# Maqam_v3a.net
KiCad netlist of a schematic drawn in EAGLE
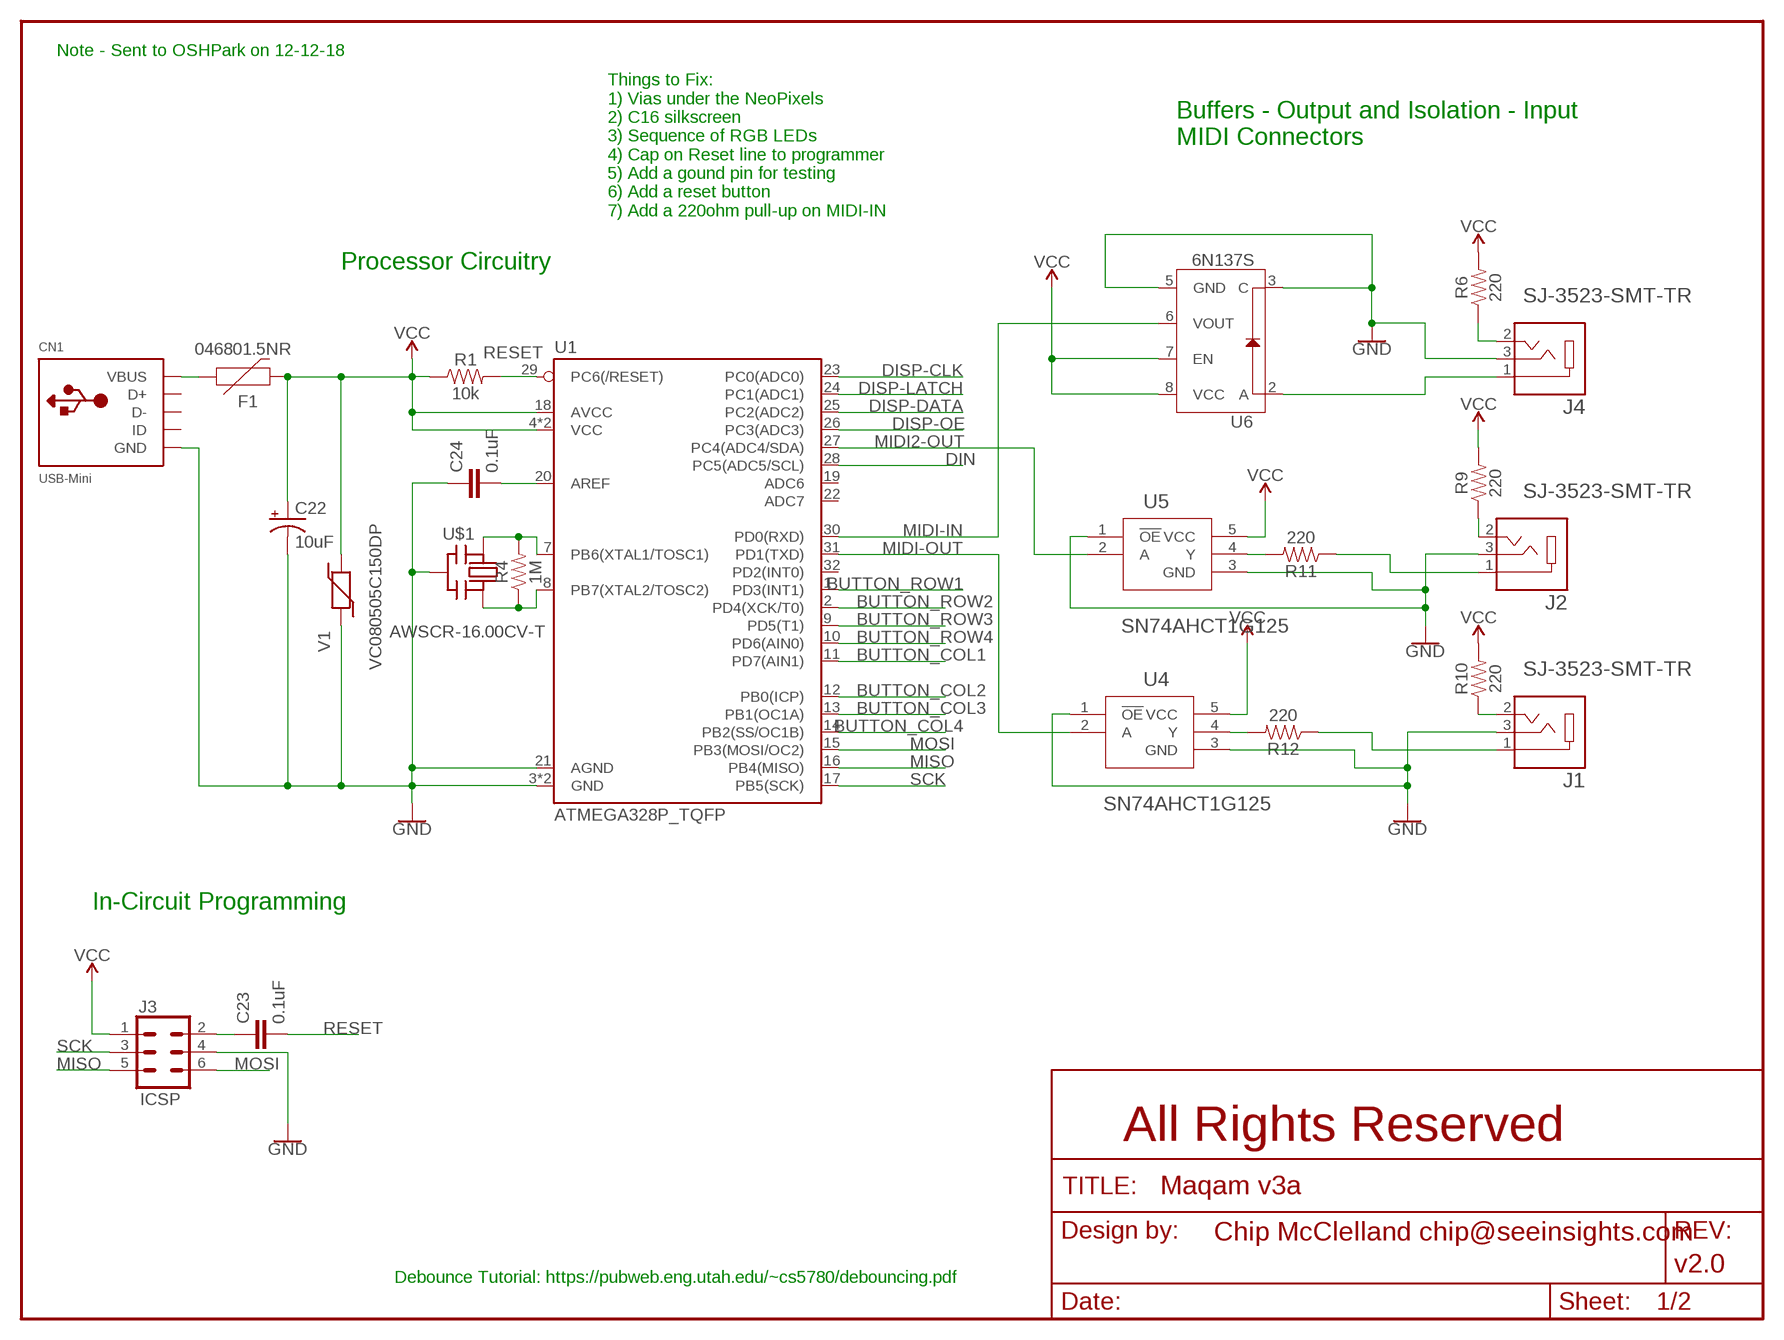
[diagram p0: schematic, sheet 1]
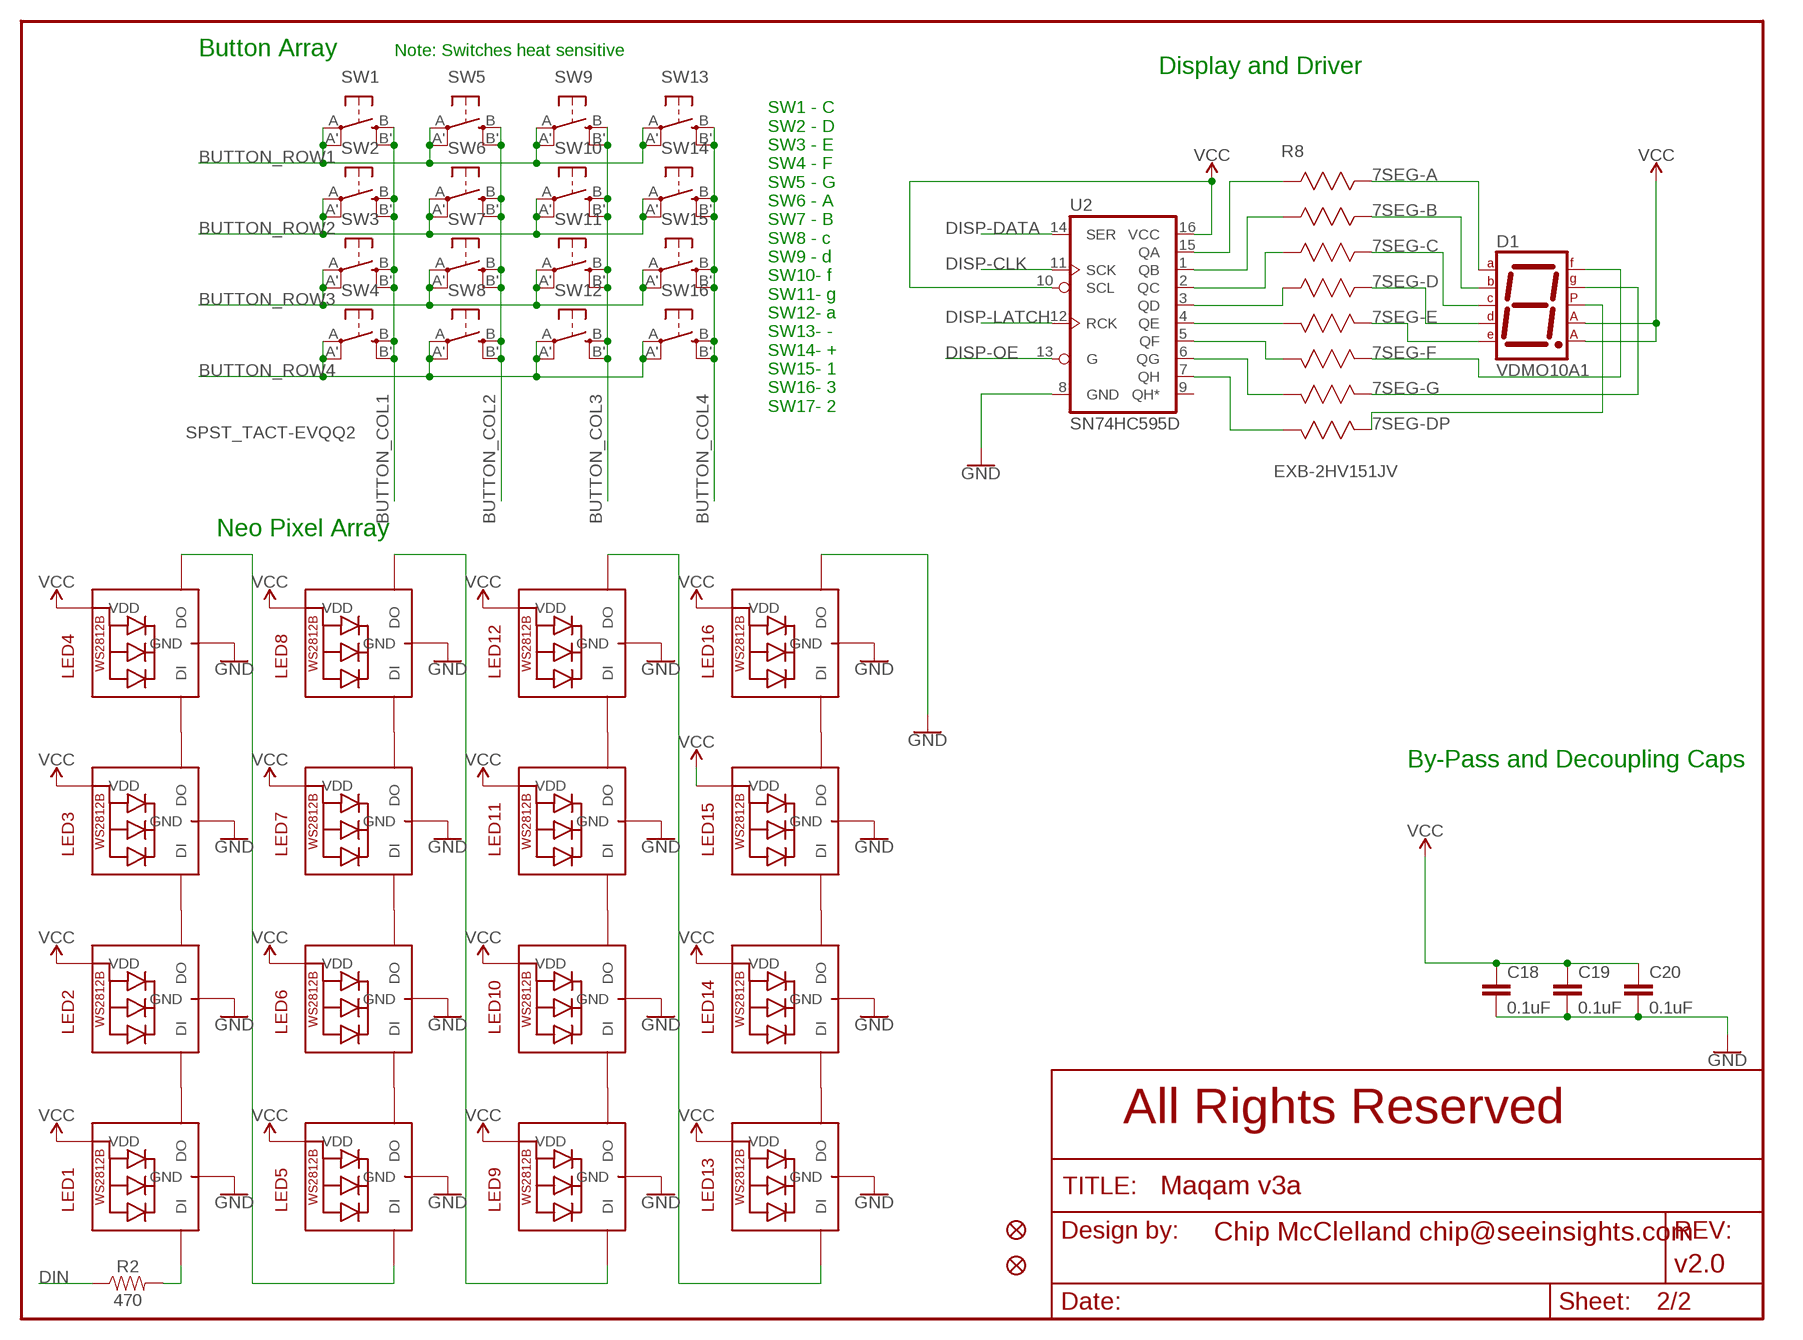
[diagram p1: schematic, sheet 2]

(export (version "E")
  (design (tool "Eeschema 10.0.6"))
  (components
    (comp (ref "C18")
      (value "0.1uF")
      (footprint "eagle-import:0805")
      (libsource (lib "eagle-import") (part "1.0UF-0805-25V-(+80/-20%)"))
    )
    (comp (ref "C19")
      (value "0.1uF")
      (footprint "eagle-import:0805")
      (libsource (lib "eagle-import") (part "1.0UF-0805-25V-(+80/-20%)"))
    )
    (comp (ref "C20")
      (value "0.1uF")
      (footprint "eagle-import:0805")
      (libsource (lib "eagle-import") (part "1.0UF-0805-25V-(+80/-20%)"))
    )
    (comp (ref "D1")
      (value "VDMO10A1")
      (footprint "eagle-import:7-SEG-SMD")
      (libsource (lib "eagle-import") (part "VDMO10A1"))
    )
    (comp (ref "FD1")
      (value "FIDUCIALUFIDUCIAL")
      (footprint "eagle-import:FIDUCIAL-MICRO")
      (libsource (lib "eagle-import") (part "FIDUCIALUFIDUCIAL"))
    )
    (comp (ref "FD2")
      (value "FIDUCIALUFIDUCIAL")
      (footprint "eagle-import:FIDUCIAL-MICRO")
      (libsource (lib "eagle-import") (part "FIDUCIALUFIDUCIAL"))
    )
    (comp (ref "FRAME1")
      (value "FRAME-LETTERNO_PACKAGE")
      (footprint "eagle-import:DUMMY")
      (fields
        (field (name "DESIGNER") "Chip McClelland chip@seeinsights.com")
        (field (name "REV") "v2.0")
        (field (name "VERSION") "v2.0")
        (field (name "DESIGNER_1") "Chip McClelland chip@seeinsights.com")
      )
      (libsource (lib "eagle-import") (part "FRAME-LETTERNO_PACKAGE"))
    )
    (comp (ref "LED1")
      (value "WS2812B3535")
      (footprint "eagle-import:LED3535")
      (libsource (lib "eagle-import") (part "WS2812B3535"))
    )
    (comp (ref "LED2")
      (value "WS2812B3535")
      (footprint "eagle-import:LED3535")
      (libsource (lib "eagle-import") (part "WS2812B3535"))
    )
    (comp (ref "LED3")
      (value "WS2812B3535")
      (footprint "eagle-import:LED3535")
      (libsource (lib "eagle-import") (part "WS2812B3535"))
    )
    (comp (ref "LED4")
      (value "WS2812B3535")
      (footprint "eagle-import:LED3535")
      (libsource (lib "eagle-import") (part "WS2812B3535"))
    )
    (comp (ref "LED5")
      (value "WS2812B3535")
      (footprint "eagle-import:LED3535")
      (libsource (lib "eagle-import") (part "WS2812B3535"))
    )
    (comp (ref "LED6")
      (value "WS2812B3535")
      (footprint "eagle-import:LED3535")
      (libsource (lib "eagle-import") (part "WS2812B3535"))
    )
    (comp (ref "LED7")
      (value "WS2812B3535")
      (footprint "eagle-import:LED3535")
      (libsource (lib "eagle-import") (part "WS2812B3535"))
    )
    (comp (ref "LED8")
      (value "WS2812B3535")
      (footprint "eagle-import:LED3535")
      (libsource (lib "eagle-import") (part "WS2812B3535"))
    )
    (comp (ref "LED9")
      (value "WS2812B3535")
      (footprint "eagle-import:LED3535")
      (libsource (lib "eagle-import") (part "WS2812B3535"))
    )
    (comp (ref "LED10")
      (value "WS2812B3535")
      (footprint "eagle-import:LED3535")
      (libsource (lib "eagle-import") (part "WS2812B3535"))
    )
    (comp (ref "LED11")
      (value "WS2812B3535")
      (footprint "eagle-import:LED3535")
      (libsource (lib "eagle-import") (part "WS2812B3535"))
    )
    (comp (ref "LED12")
      (value "WS2812B3535")
      (footprint "eagle-import:LED3535")
      (libsource (lib "eagle-import") (part "WS2812B3535"))
    )
    (comp (ref "LED13")
      (value "WS2812B3535")
      (footprint "eagle-import:LED3535")
      (libsource (lib "eagle-import") (part "WS2812B3535"))
    )
    (comp (ref "LED14")
      (value "WS2812B3535")
      (footprint "eagle-import:LED3535")
      (libsource (lib "eagle-import") (part "WS2812B3535"))
    )
    (comp (ref "LED15")
      (value "WS2812B3535")
      (footprint "eagle-import:LED3535")
      (libsource (lib "eagle-import") (part "WS2812B3535"))
    )
    (comp (ref "LED16")
      (value "WS2812B3535")
      (footprint "eagle-import:LED3535")
      (libsource (lib "eagle-import") (part "WS2812B3535"))
    )
    (comp (ref "R2")
      (value "470")
      (footprint "eagle-import:0805")
      (libsource (lib "eagle-import") (part "RESISTOR0805"))
    )
    (comp (ref "R8")
      (value "EXB-2HV151JV")
      (footprint "eagle-import:EXB2HV-L")
      (fields (field (name "MANUFACTURER_PART_NUMBER") "EXB2HV103JV"))
      (libsource (lib "eagle-import") (part "EXB-2HV103JVEXB2HV-L"))
    )
    (comp (ref "SW1")
      (value "SPST_TACT-EVQQ2")
      (footprint "eagle-import:EVQ-Q2")
      (libsource (lib "eagle-import") (part "SPST_TACT-EVQQ2"))
    )
    (comp (ref "SW2")
      (value "SPST_TACT-EVQQ2")
      (footprint "eagle-import:EVQ-Q2")
      (libsource (lib "eagle-import") (part "SPST_TACT-EVQQ2"))
    )
    (comp (ref "SW3")
      (value "SPST_TACT-EVQQ2")
      (footprint "eagle-import:EVQ-Q2")
      (libsource (lib "eagle-import") (part "SPST_TACT-EVQQ2"))
    )
    (comp (ref "SW4")
      (value "SPST_TACT-EVQQ2")
      (footprint "eagle-import:EVQ-Q2")
      (libsource (lib "eagle-import") (part "SPST_TACT-EVQQ2"))
    )
    (comp (ref "SW5")
      (value "SPST_TACT-EVQQ2")
      (footprint "eagle-import:EVQ-Q2")
      (libsource (lib "eagle-import") (part "SPST_TACT-EVQQ2"))
    )
    (comp (ref "SW6")
      (value "SPST_TACT-EVQQ2")
      (footprint "eagle-import:EVQ-Q2")
      (libsource (lib "eagle-import") (part "SPST_TACT-EVQQ2"))
    )
    (comp (ref "SW7")
      (value "SPST_TACT-EVQQ2")
      (footprint "eagle-import:EVQ-Q2")
      (libsource (lib "eagle-import") (part "SPST_TACT-EVQQ2"))
    )
    (comp (ref "SW8")
      (value "SPST_TACT-EVQQ2")
      (footprint "eagle-import:EVQ-Q2")
      (libsource (lib "eagle-import") (part "SPST_TACT-EVQQ2"))
    )
    (comp (ref "SW9")
      (value "SPST_TACT-EVQQ2")
      (footprint "eagle-import:EVQ-Q2")
      (libsource (lib "eagle-import") (part "SPST_TACT-EVQQ2"))
    )
    (comp (ref "SW10")
      (value "SPST_TACT-EVQQ2")
      (footprint "eagle-import:EVQ-Q2")
      (libsource (lib "eagle-import") (part "SPST_TACT-EVQQ2"))
    )
    (comp (ref "SW11")
      (value "SPST_TACT-EVQQ2")
      (footprint "eagle-import:EVQ-Q2")
      (libsource (lib "eagle-import") (part "SPST_TACT-EVQQ2"))
    )
    (comp (ref "SW12")
      (value "SPST_TACT-EVQQ2")
      (footprint "eagle-import:EVQ-Q2")
      (libsource (lib "eagle-import") (part "SPST_TACT-EVQQ2"))
    )
    (comp (ref "SW13")
      (value "SPST_TACT-EVQQ2")
      (footprint "eagle-import:EVQ-Q2")
      (libsource (lib "eagle-import") (part "SPST_TACT-EVQQ2"))
    )
    (comp (ref "SW14")
      (value "SPST_TACT-EVQQ2")
      (footprint "eagle-import:EVQ-Q2")
      (libsource (lib "eagle-import") (part "SPST_TACT-EVQQ2"))
    )
    (comp (ref "SW15")
      (value "SPST_TACT-EVQQ2")
      (footprint "eagle-import:EVQ-Q2")
      (libsource (lib "eagle-import") (part "SPST_TACT-EVQQ2"))
    )
    (comp (ref "SW16")
      (value "SPST_TACT-EVQQ2")
      (footprint "eagle-import:EVQ-Q2")
      (libsource (lib "eagle-import") (part "SPST_TACT-EVQQ2"))
    )
    (comp (ref "U2")
      (value "SN74HC595D")
      (footprint "eagle-import:SO16")
      (libsource (lib "eagle-import") (part "74595DHC"))
    )
    (comp (ref "C22")
      (value "10uF")
      (footprint "eagle-import:EIA3216")
      (libsource (lib "eagle-import") (part "10UF-POLAR-EIA3216-16V-10%(TANT)"))
    )
    (comp (ref "C23")
      (value "0.1uF")
      (footprint "eagle-import:0805")
      (libsource (lib "eagle-import") (part "1.0UF-0805-25V-(+80/-20%)"))
    )
    (comp (ref "C24")
      (value "0.1uF")
      (footprint "eagle-import:0805")
      (libsource (lib "eagle-import") (part "1.0UF-0805-25V-(+80/-20%)"))
    )
    (comp (ref "CN1")
      (value "USB-Mini")
      (footprint "eagle-import:USB-MINIB")
      (libsource (lib "eagle-import") (part "USBMINIB"))
    )
    (comp (ref "F1")
      (value "046801.5NR")
      (footprint "eagle-import:1206")
      (libsource (lib "eagle-import") (part "PPTC_HALF-AMP"))
    )
    (comp (ref "FRAME2")
      (value "FRAME-LETTERNO_PACKAGE")
      (footprint "eagle-import:DUMMY")
      (fields
        (field (name "DESIGNER") "Chip McClelland chip@seeinsights.com")
        (field (name "REV") "v2.0")
        (field (name "VERSION") "v2.0")
        (field (name "DESIGNER_1") "Chip McClelland chip@seeinsights.com")
      )
      (libsource (lib "eagle-import") (part "FRAME-LETTERNO_PACKAGE"))
    )
    (comp (ref "J1")
      (value "SJ-3523-SMT-TR")
      (footprint "eagle-import:CUI_SJ-3523-SMT-TR")
      (fields (field (name "DIGI-KEY_PART_NUMBER") "CP-3523SJCT-ND") (field (name "MF") "CUI Inc."))
      (libsource (lib "eagle-import") (part "SJ-3523-SMT-TR"))
    )
    (comp (ref "J2")
      (value "SJ-3523-SMT-TR")
      (footprint "eagle-import:CUI_SJ-3523-SMT-TR")
      (fields (field (name "DIGI-KEY_PART_NUMBER") "CP-3523SJCT-ND") (field (name "MF") "CUI Inc."))
      (libsource (lib "eagle-import") (part "SJ-3523-SMT-TR"))
    )
    (comp (ref "J3")
      (value "ICSP")
      (footprint "eagle-import:2X3-SHROUDED")
      (libsource (lib "eagle-import") (part "CONN_03X2SHROUD"))
    )
    (comp (ref "J4")
      (value "SJ-3523-SMT-TR")
      (footprint "eagle-import:CUI_SJ-3523-SMT-TR")
      (fields (field (name "DIGI-KEY_PART_NUMBER") "CP-3523SJCT-ND") (field (name "MF") "CUI Inc."))
      (libsource (lib "eagle-import") (part "SJ-3523-SMT-TR"))
    )
    (comp (ref "R1")
      (value "10k")
      (footprint "eagle-import:0805")
      (libsource (lib "eagle-import") (part "RESISTOR0805"))
    )
    (comp (ref "R4")
      (value "1M")
      (footprint "eagle-import:0805")
      (libsource (lib "eagle-import") (part "RESISTOR0805"))
    )
    (comp (ref "R6")
      (value "220")
      (footprint "eagle-import:0805")
      (libsource (lib "eagle-import") (part "RESISTOR0805"))
    )
    (comp (ref "R9")
      (value "220")
      (footprint "eagle-import:0805")
      (libsource (lib "eagle-import") (part "RESISTOR0805"))
    )
    (comp (ref "R10")
      (value "220")
      (footprint "eagle-import:0805")
      (libsource (lib "eagle-import") (part "RESISTOR0805"))
    )
    (comp (ref "R11")
      (value "220")
      (footprint "eagle-import:0805")
      (libsource (lib "eagle-import") (part "RESISTOR0805"))
    )
    (comp (ref "R12")
      (value "220")
      (footprint "eagle-import:0805")
      (libsource (lib "eagle-import") (part "RESISTOR0805"))
    )
    (comp (ref "U$1")
      (value "AWSCR-16.00CV-T")
      (footprint "eagle-import:AWSCR")
      (libsource (lib "eagle-import") (part "CERMOSCILL"))
    )
    (comp (ref "U1")
      (value "ATMEGA328P_TQFP")
      (footprint "eagle-import:TQFP32-08")
      (libsource (lib "eagle-import") (part "ATMEGA328P_TQFP"))
    )
    (comp (ref "U4")
      (value "SN74AHCT1G125")
      (footprint "eagle-import:DBV5-L")
      (fields (field (name "MANUFACTURER_PART_NUMBER") "SN74AHCT1G125DBVR"))
      (libsource (lib "eagle-import") (part "SN74AHCT1G125DBVRDBV5-L"))
    )
    (comp (ref "U5")
      (value "SN74AHCT1G125")
      (footprint "eagle-import:DBV5-L")
      (fields (field (name "MANUFACTURER_PART_NUMBER") "SN74AHCT1G125DBVR"))
      (libsource (lib "eagle-import") (part "SN74AHCT1G125DBVRDBV5-L"))
    )
    (comp (ref "U6")
      (value "6N137S")
      (footprint "eagle-import:8-SMD")
      (libsource (lib "eagle-import") (part "6N137S"))
    )
    (comp (ref "V1")
      (value "VC080505C150DP")
      (footprint "eagle-import:0805")
      (libsource (lib "eagle-import") (part "VARISTOR"))
    )
  )
  (nets
    (net (code "1") (name "7SEG-A") (class "Default")
      (node (ref "D1") (pin "7SEG7") (pinfunction "A_7SEG7") (pintype "passive"))
      (node (ref "R8") (pin "16") (pinfunction "162_16") (pintype "passive"))
    )
    (net (code "2") (name "7SEG-B") (class "Default")
      (node (ref "D1") (pin "7SEG6") (pinfunction "B_7SEG6") (pintype "passive"))
      (node (ref "R8") (pin "15") (pinfunction "154_15") (pintype "passive"))
    )
    (net (code "3") (name "7SEG-C") (class "Default")
      (node (ref "D1") (pin "7SEG4") (pinfunction "C_7SEG4") (pintype "passive"))
      (node (ref "R8") (pin "14") (pinfunction "146_14") (pintype "passive"))
    )
    (net (code "4") (name "7SEG-D") (class "Default")
      (node (ref "D1") (pin "7SEG2") (pinfunction "D_7SEG2") (pintype "passive"))
      (node (ref "R8") (pin "13") (pinfunction "138_13") (pintype "passive"))
    )
    (net (code "5") (name "7SEG-DP") (class "Default")
      (node (ref "D1") (pin "7SEG5") (pinfunction "DP_7SEG5") (pintype "passive"))
      (node (ref "R8") (pin "9") (pinfunction "912_9") (pintype "passive"))
    )
    (net (code "6") (name "7SEG-E") (class "Default")
      (node (ref "D1") (pin "7SEG1") (pinfunction "E_7SEG1") (pintype "passive"))
      (node (ref "R8") (pin "12") (pinfunction "1211_12") (pintype "passive"))
    )
    (net (code "7") (name "7SEG-F") (class "Default")
      (node (ref "D1") (pin "7SEG9") (pinfunction "F_7SEG9") (pintype "passive"))
      (node (ref "R8") (pin "11") (pinfunction "1110_11") (pintype "passive"))
    )
    (net (code "8") (name "7SEG-G") (class "Default")
      (node (ref "D1") (pin "7SEG10") (pinfunction "G_7SEG10") (pintype "passive"))
      (node (ref "R8") (pin "10") (pinfunction "109_10") (pintype "passive"))
    )
    (net (code "9") (name "BUTTON_COL1") (class "Default")
      (node (ref "SW1") (pin "B") (pinfunction "S_B") (pintype "passive"))
      (node (ref "SW1") (pin "B'") (pinfunction "S1_B'") (pintype "passive"))
      (node (ref "SW2") (pin "B") (pinfunction "S_B") (pintype "passive"))
      (node (ref "SW2") (pin "B'") (pinfunction "S1_B'") (pintype "passive"))
      (node (ref "SW3") (pin "B") (pinfunction "S_B") (pintype "passive"))
      (node (ref "SW3") (pin "B'") (pinfunction "S1_B'") (pintype "passive"))
      (node (ref "SW4") (pin "B") (pinfunction "S_B") (pintype "passive"))
      (node (ref "SW4") (pin "B'") (pinfunction "S1_B'") (pintype "passive"))
      (node (ref "U1") (pin "11") (pinfunction "PD7(AIN1)_11") (pintype "bidirectional"))
    )
    (net (code "10") (name "BUTTON_COL2") (class "Default")
      (node (ref "SW5") (pin "B") (pinfunction "S_B") (pintype "passive"))
      (node (ref "SW5") (pin "B'") (pinfunction "S1_B'") (pintype "passive"))
      (node (ref "SW6") (pin "B") (pinfunction "S_B") (pintype "passive"))
      (node (ref "SW6") (pin "B'") (pinfunction "S1_B'") (pintype "passive"))
      (node (ref "SW7") (pin "B") (pinfunction "S_B") (pintype "passive"))
      (node (ref "SW7") (pin "B'") (pinfunction "S1_B'") (pintype "passive"))
      (node (ref "SW8") (pin "B") (pinfunction "S_B") (pintype "passive"))
      (node (ref "SW8") (pin "B'") (pinfunction "S1_B'") (pintype "passive"))
      (node (ref "U1") (pin "12") (pinfunction "PB0(ICP)_12") (pintype "bidirectional"))
    )
    (net (code "11") (name "BUTTON_COL3") (class "Default")
      (node (ref "SW10") (pin "B") (pinfunction "S_B") (pintype "passive"))
      (node (ref "SW10") (pin "B'") (pinfunction "S1_B'") (pintype "passive"))
      (node (ref "SW11") (pin "B") (pinfunction "S_B") (pintype "passive"))
      (node (ref "SW11") (pin "B'") (pinfunction "S1_B'") (pintype "passive"))
      (node (ref "SW12") (pin "B") (pinfunction "S_B") (pintype "passive"))
      (node (ref "SW12") (pin "B'") (pinfunction "S1_B'") (pintype "passive"))
      (node (ref "SW9") (pin "B") (pinfunction "S_B") (pintype "passive"))
      (node (ref "SW9") (pin "B'") (pinfunction "S1_B'") (pintype "passive"))
      (node (ref "U1") (pin "13") (pinfunction "PB1(OC1A)_13") (pintype "bidirectional"))
    )
    (net (code "12") (name "BUTTON_COL4") (class "Default")
      (node (ref "SW13") (pin "B") (pinfunction "S_B") (pintype "passive"))
      (node (ref "SW13") (pin "B'") (pinfunction "S1_B'") (pintype "passive"))
      (node (ref "SW14") (pin "B") (pinfunction "S_B") (pintype "passive"))
      (node (ref "SW14") (pin "B'") (pinfunction "S1_B'") (pintype "passive"))
      (node (ref "SW15") (pin "B") (pinfunction "S_B") (pintype "passive"))
      (node (ref "SW15") (pin "B'") (pinfunction "S1_B'") (pintype "passive"))
      (node (ref "SW16") (pin "B") (pinfunction "S_B") (pintype "passive"))
      (node (ref "SW16") (pin "B'") (pinfunction "S1_B'") (pintype "passive"))
      (node (ref "U1") (pin "14") (pinfunction "PB2(SS/OC1B)_14") (pintype "bidirectional"))
    )
    (net (code "13") (name "BUTTON_ROW1") (class "Default")
      (node (ref "SW1") (pin "A") (pinfunction "P_A") (pintype "passive"))
      (node (ref "SW1") (pin "A'") (pinfunction "P1_A'") (pintype "passive"))
      (node (ref "SW13") (pin "A") (pinfunction "P_A") (pintype "passive"))
      (node (ref "SW13") (pin "A'") (pinfunction "P1_A'") (pintype "passive"))
      (node (ref "SW5") (pin "A") (pinfunction "P_A") (pintype "passive"))
      (node (ref "SW5") (pin "A'") (pinfunction "P1_A'") (pintype "passive"))
      (node (ref "SW9") (pin "A") (pinfunction "P_A") (pintype "passive"))
      (node (ref "SW9") (pin "A'") (pinfunction "P1_A'") (pintype "passive"))
      (node (ref "U1") (pin "1") (pinfunction "PD3(INT1)_1") (pintype "bidirectional"))
    )
    (net (code "14") (name "BUTTON_ROW2") (class "Default")
      (node (ref "SW10") (pin "A") (pinfunction "P_A") (pintype "passive"))
      (node (ref "SW10") (pin "A'") (pinfunction "P1_A'") (pintype "passive"))
      (node (ref "SW14") (pin "A") (pinfunction "P_A") (pintype "passive"))
      (node (ref "SW14") (pin "A'") (pinfunction "P1_A'") (pintype "passive"))
      (node (ref "SW2") (pin "A") (pinfunction "P_A") (pintype "passive"))
      (node (ref "SW2") (pin "A'") (pinfunction "P1_A'") (pintype "passive"))
      (node (ref "SW6") (pin "A") (pinfunction "P_A") (pintype "passive"))
      (node (ref "SW6") (pin "A'") (pinfunction "P1_A'") (pintype "passive"))
      (node (ref "U1") (pin "2") (pinfunction "PD4(XCK/T0)_2") (pintype "bidirectional"))
    )
    (net (code "15") (name "BUTTON_ROW3") (class "Default")
      (node (ref "SW11") (pin "A") (pinfunction "P_A") (pintype "passive"))
      (node (ref "SW11") (pin "A'") (pinfunction "P1_A'") (pintype "passive"))
      (node (ref "SW15") (pin "A") (pinfunction "P_A") (pintype "passive"))
      (node (ref "SW15") (pin "A'") (pinfunction "P1_A'") (pintype "passive"))
      (node (ref "SW3") (pin "A") (pinfunction "P_A") (pintype "passive"))
      (node (ref "SW3") (pin "A'") (pinfunction "P1_A'") (pintype "passive"))
      (node (ref "SW7") (pin "A") (pinfunction "P_A") (pintype "passive"))
      (node (ref "SW7") (pin "A'") (pinfunction "P1_A'") (pintype "passive"))
      (node (ref "U1") (pin "9") (pinfunction "PD5(T1)_9") (pintype "bidirectional"))
    )
    (net (code "16") (name "BUTTON_ROW4") (class "Default")
      (node (ref "SW12") (pin "A") (pinfunction "P_A") (pintype "passive"))
      (node (ref "SW12") (pin "A'") (pinfunction "P1_A'") (pintype "passive"))
      (node (ref "SW16") (pin "A") (pinfunction "P_A") (pintype "passive"))
      (node (ref "SW16") (pin "A'") (pinfunction "P1_A'") (pintype "passive"))
      (node (ref "SW4") (pin "A") (pinfunction "P_A") (pintype "passive"))
      (node (ref "SW4") (pin "A'") (pinfunction "P1_A'") (pintype "passive"))
      (node (ref "SW8") (pin "A") (pinfunction "P_A") (pintype "passive"))
      (node (ref "SW8") (pin "A'") (pinfunction "P1_A'") (pintype "passive"))
      (node (ref "U1") (pin "10") (pinfunction "PD6(AIN0)_10") (pintype "bidirectional"))
    )
    (net (code "17") (name "DIN") (class "Default")
      (node (ref "R2") (pin "1") (pinfunction "1_1") (pintype "passive"))
      (node (ref "U1") (pin "28") (pinfunction "PC5(ADC5/SCL)_28") (pintype "bidirectional"))
    )
    (net (code "18") (name "DISP-CLK") (class "Default")
      (node (ref "U1") (pin "23") (pinfunction "PC0(ADC0)_23") (pintype "bidirectional"))
      (node (ref "U2") (pin "11") (pinfunction "SCK_11") (pintype "input"))
    )
    (net (code "19") (name "DISP-DATA") (class "Default")
      (node (ref "U1") (pin "25") (pinfunction "PC2(ADC2)_25") (pintype "bidirectional"))
      (node (ref "U2") (pin "14") (pinfunction "SER_14") (pintype "input"))
    )
    (net (code "20") (name "DISP-LATCH") (class "Default")
      (node (ref "U1") (pin "24") (pinfunction "PC1(ADC1)_24") (pintype "bidirectional"))
      (node (ref "U2") (pin "12") (pinfunction "RCK_12") (pintype "input"))
    )
    (net (code "21") (name "DISP-OE") (class "Default")
      (node (ref "U1") (pin "26") (pinfunction "PC3(ADC3)_26") (pintype "bidirectional"))
      (node (ref "U2") (pin "13") (pinfunction "G_13") (pintype "input"))
    )
    (net (code "22") (name "GND") (class "Default")
      (node (ref "C18") (pin "2") (pinfunction "2_2") (pintype "passive"))
      (node (ref "C19") (pin "2") (pinfunction "2_2") (pintype "passive"))
      (node (ref "C20") (pin "2") (pinfunction "2_2") (pintype "passive"))
      (node (ref "C22") (pin "-") (pinfunction "-_-") (pintype "passive"))
      (node (ref "C24") (pin "1") (pinfunction "1_1") (pintype "passive"))
      (node (ref "CN1") (pin "GND") (pinfunction "GND_GND") (pintype "power_in"))
      (node (ref "J1") (pin "3") (pinfunction "3_3") (pintype "passive"))
      (node (ref "J2") (pin "3") (pinfunction "3_3") (pintype "passive"))
      (node (ref "J3") (pin "4") (pinfunction "4_4") (pintype "bidirectional"))
      (node (ref "J4") (pin "3") (pinfunction "3_3") (pintype "passive"))
      (node (ref "LED1") (pin "4") (pinfunction "GND_4") (pintype "power_in"))
      (node (ref "LED10") (pin "4") (pinfunction "GND_4") (pintype "power_in"))
      (node (ref "LED11") (pin "4") (pinfunction "GND_4") (pintype "power_in"))
      (node (ref "LED12") (pin "4") (pinfunction "GND_4") (pintype "power_in"))
      (node (ref "LED13") (pin "4") (pinfunction "GND_4") (pintype "power_in"))
      (node (ref "LED14") (pin "4") (pinfunction "GND_4") (pintype "power_in"))
      (node (ref "LED15") (pin "4") (pinfunction "GND_4") (pintype "power_in"))
      (node (ref "LED16") (pin "3") (pinfunction "DO_3") (pintype "output"))
      (node (ref "LED16") (pin "4") (pinfunction "GND_4") (pintype "power_in"))
      (node (ref "LED2") (pin "4") (pinfunction "GND_4") (pintype "power_in"))
      (node (ref "LED3") (pin "4") (pinfunction "GND_4") (pintype "power_in"))
      (node (ref "LED4") (pin "4") (pinfunction "GND_4") (pintype "power_in"))
      (node (ref "LED5") (pin "4") (pinfunction "GND_4") (pintype "power_in"))
      (node (ref "LED6") (pin "4") (pinfunction "GND_4") (pintype "power_in"))
      (node (ref "LED7") (pin "4") (pinfunction "GND_4") (pintype "power_in"))
      (node (ref "LED8") (pin "4") (pinfunction "GND_4") (pintype "power_in"))
      (node (ref "LED9") (pin "4") (pinfunction "GND_4") (pintype "power_in"))
      (node (ref "U$1") (pin "2") (pinfunction "GND_2") (pintype "bidirectional"))
      (node (ref "U1") (pin "21") (pinfunction "AGND_21") (pintype "bidirectional"))
      (node (ref "U1") (pin "3") (pinfunction "GND_3") (pintype "bidirectional"))
      (node (ref "U1") (pin "5") (pinfunction "GND_5") (pintype "bidirectional"))
      (node (ref "U2") (pin "8") (pinfunction "GND_8") (pintype "power_in"))
      (node (ref "U4") (pin "1") (pinfunction "~{OE}_1") (pintype "input"))
      (node (ref "U4") (pin "3") (pinfunction "GND_3") (pintype "power_in"))
      (node (ref "U5") (pin "1") (pinfunction "~{OE}_1") (pintype "input"))
      (node (ref "U5") (pin "3") (pinfunction "GND_3") (pintype "power_in"))
      (node (ref "U6") (pin "3") (pinfunction "C_3") (pintype "bidirectional"))
      (node (ref "U6") (pin "5") (pinfunction "GND_5") (pintype "bidirectional"))
      (node (ref "V1") (pin "1") (pinfunction "1_1") (pintype "passive"))
    )
    (net (code "23") (name "MIDI-IN") (class "Default")
      (node (ref "U1") (pin "30") (pinfunction "PD0(RXD)_30") (pintype "bidirectional"))
      (node (ref "U6") (pin "6") (pinfunction "VOUT_6") (pintype "bidirectional"))
    )
    (net (code "24") (name "MIDI-OUT") (class "Default")
      (node (ref "U1") (pin "31") (pinfunction "PD1(TXD)_31") (pintype "bidirectional"))
      (node (ref "U4") (pin "2") (pinfunction "A_2") (pintype "input"))
    )
    (net (code "25") (name "MIDI2-OUT") (class "Default")
      (node (ref "U1") (pin "27") (pinfunction "PC4(ADC4/SDA)_27") (pintype "bidirectional"))
      (node (ref "U5") (pin "2") (pinfunction "A_2") (pintype "input"))
    )
    (net (code "26") (name "MISO") (class "Default")
      (node (ref "J3") (pin "5") (pinfunction "5_5") (pintype "bidirectional"))
      (node (ref "U1") (pin "16") (pinfunction "PB4(MISO)_16") (pintype "bidirectional"))
    )
    (net (code "27") (name "MOSI") (class "Default")
      (node (ref "J3") (pin "6") (pinfunction "6_6") (pintype "bidirectional"))
      (node (ref "U1") (pin "15") (pinfunction "PB3(MOSI/OC2)_15") (pintype "bidirectional"))
    )
    (net (code "28") (name "Net-(C23-Pad1)") (class "Default")
      (node (ref "C23") (pin "1") (pinfunction "1_1") (pintype "passive"))
      (node (ref "J3") (pin "2") (pinfunction "2_2") (pintype "bidirectional"))
    )
    (net (code "29") (name "Net-(CN1-PadVBUS)") (class "Default")
      (node (ref "CN1") (pin "VBUS") (pinfunction "VBUS_VBUS") (pintype "power_in"))
      (node (ref "F1") (pin "1") (pinfunction "1_1") (pintype "bidirectional"))
    )
    (net (code "30") (name "Net-(J1-Pad1)") (class "Default")
      (node (ref "J1") (pin "1") (pinfunction "1_1") (pintype "passive"))
      (node (ref "R12") (pin "1") (pinfunction "1_1") (pintype "passive"))
    )
    (net (code "31") (name "Net-(J1-Pad2)") (class "Default")
      (node (ref "J1") (pin "2") (pinfunction "2_2") (pintype "passive"))
      (node (ref "R10") (pin "1") (pinfunction "1_1") (pintype "passive"))
    )
    (net (code "32") (name "Net-(J2-Pad1)") (class "Default")
      (node (ref "J2") (pin "1") (pinfunction "1_1") (pintype "passive"))
      (node (ref "R11") (pin "1") (pinfunction "1_1") (pintype "passive"))
    )
    (net (code "33") (name "Net-(J2-Pad2)") (class "Default")
      (node (ref "J2") (pin "2") (pinfunction "2_2") (pintype "passive"))
      (node (ref "R9") (pin "1") (pinfunction "1_1") (pintype "passive"))
    )
    (net (code "34") (name "Net-(J4-Pad2)") (class "Default")
      (node (ref "J4") (pin "2") (pinfunction "2_2") (pintype "passive"))
      (node (ref "R6") (pin "1") (pinfunction "1_1") (pintype "passive"))
    )
    (net (code "35") (name "Net-(LED1-DI)") (class "Default")
      (node (ref "LED1") (pin "1") (pinfunction "DI_1") (pintype "input"))
      (node (ref "R2") (pin "2") (pinfunction "2_2") (pintype "passive"))
    )
    (net (code "36") (name "Net-(LED1-DO)") (class "Default")
      (node (ref "LED1") (pin "3") (pinfunction "DO_3") (pintype "output"))
      (node (ref "LED2") (pin "1") (pinfunction "DI_1") (pintype "input"))
    )
    (net (code "37") (name "Net-(LED2-DO)") (class "Default")
      (node (ref "LED2") (pin "3") (pinfunction "DO_3") (pintype "output"))
      (node (ref "LED3") (pin "1") (pinfunction "DI_1") (pintype "input"))
    )
    (net (code "38") (name "Net-(LED3-DO)") (class "Default")
      (node (ref "LED3") (pin "3") (pinfunction "DO_3") (pintype "output"))
      (node (ref "LED4") (pin "1") (pinfunction "DI_1") (pintype "input"))
    )
    (net (code "39") (name "Net-(LED4-DO)") (class "Default")
      (node (ref "LED4") (pin "3") (pinfunction "DO_3") (pintype "output"))
      (node (ref "LED5") (pin "1") (pinfunction "DI_1") (pintype "input"))
    )
    (net (code "40") (name "Net-(LED5-DO)") (class "Default")
      (node (ref "LED5") (pin "3") (pinfunction "DO_3") (pintype "output"))
      (node (ref "LED6") (pin "1") (pinfunction "DI_1") (pintype "input"))
    )
    (net (code "41") (name "Net-(LED6-DO)") (class "Default")
      (node (ref "LED6") (pin "3") (pinfunction "DO_3") (pintype "output"))
      (node (ref "LED7") (pin "1") (pinfunction "DI_1") (pintype "input"))
    )
    (net (code "42") (name "Net-(LED7-DO)") (class "Default")
      (node (ref "LED7") (pin "3") (pinfunction "DO_3") (pintype "output"))
      (node (ref "LED8") (pin "1") (pinfunction "DI_1") (pintype "input"))
    )
    (net (code "43") (name "Net-(LED8-DO)") (class "Default")
      (node (ref "LED8") (pin "3") (pinfunction "DO_3") (pintype "output"))
      (node (ref "LED9") (pin "1") (pinfunction "DI_1") (pintype "input"))
    )
    (net (code "44") (name "Net-(LED10-DI)") (class "Default")
      (node (ref "LED10") (pin "1") (pinfunction "DI_1") (pintype "input"))
      (node (ref "LED9") (pin "3") (pinfunction "DO_3") (pintype "output"))
    )
    (net (code "45") (name "Net-(LED10-DO)") (class "Default")
      (node (ref "LED10") (pin "3") (pinfunction "DO_3") (pintype "output"))
      (node (ref "LED11") (pin "1") (pinfunction "DI_1") (pintype "input"))
    )
    (net (code "46") (name "Net-(LED11-DO)") (class "Default")
      (node (ref "LED11") (pin "3") (pinfunction "DO_3") (pintype "output"))
      (node (ref "LED12") (pin "1") (pinfunction "DI_1") (pintype "input"))
    )
    (net (code "47") (name "Net-(LED12-DO)") (class "Default")
      (node (ref "LED12") (pin "3") (pinfunction "DO_3") (pintype "output"))
      (node (ref "LED13") (pin "1") (pinfunction "DI_1") (pintype "input"))
    )
    (net (code "48") (name "Net-(LED13-DO)") (class "Default")
      (node (ref "LED13") (pin "3") (pinfunction "DO_3") (pintype "output"))
      (node (ref "LED14") (pin "1") (pinfunction "DI_1") (pintype "input"))
    )
    (net (code "49") (name "Net-(LED14-DO)") (class "Default")
      (node (ref "LED14") (pin "3") (pinfunction "DO_3") (pintype "output"))
      (node (ref "LED15") (pin "1") (pinfunction "DI_1") (pintype "input"))
    )
    (net (code "50") (name "Net-(LED15-DO)") (class "Default")
      (node (ref "LED15") (pin "3") (pinfunction "DO_3") (pintype "output"))
      (node (ref "LED16") (pin "1") (pinfunction "DI_1") (pintype "input"))
    )
    (net (code "51") (name "Net-(R8-11)") (class "Default")
      (node (ref "R8") (pin "1") (pinfunction "11_1") (pintype "passive"))
      (node (ref "U2") (pin "15") (pinfunction "QA_15") (pintype "tri_state"))
    )
    (net (code "52") (name "Net-(R8-23)") (class "Default")
      (node (ref "R8") (pin "2") (pinfunction "23_2") (pintype "passive"))
      (node (ref "U2") (pin "1") (pinfunction "QB_1") (pintype "tri_state"))
    )
    (net (code "53") (name "Net-(R8-35)") (class "Default")
      (node (ref "R8") (pin "3") (pinfunction "35_3") (pintype "passive"))
      (node (ref "U2") (pin "2") (pinfunction "QC_2") (pintype "tri_state"))
    )
    (net (code "54") (name "Net-(R8-47)") (class "Default")
      (node (ref "R8") (pin "4") (pinfunction "47_4") (pintype "passive"))
      (node (ref "U2") (pin "3") (pinfunction "QD_3") (pintype "tri_state"))
    )
    (net (code "55") (name "Net-(R8-516)") (class "Default")
      (node (ref "R8") (pin "5") (pinfunction "516_5") (pintype "passive"))
      (node (ref "U2") (pin "4") (pinfunction "QE_4") (pintype "tri_state"))
    )
    (net (code "56") (name "Net-(R8-615)") (class "Default")
      (node (ref "R8") (pin "6") (pinfunction "615_6") (pintype "passive"))
      (node (ref "U2") (pin "5") (pinfunction "QF_5") (pintype "tri_state"))
    )
    (net (code "57") (name "Net-(R8-714)") (class "Default")
      (node (ref "R8") (pin "7") (pinfunction "714_7") (pintype "passive"))
      (node (ref "U2") (pin "6") (pinfunction "QG_6") (pintype "tri_state"))
    )
    (net (code "58") (name "Net-(R8-813)") (class "Default")
      (node (ref "R8") (pin "8") (pinfunction "813_8") (pintype "passive"))
      (node (ref "U2") (pin "7") (pinfunction "QH_7") (pintype "tri_state"))
    )
    (net (code "59") (name "Net-(U$1-IN)") (class "Default")
      (node (ref "R4") (pin "2") (pinfunction "2_2") (pintype "passive"))
      (node (ref "U$1") (pin "1") (pinfunction "IN_1") (pintype "bidirectional"))
      (node (ref "U1") (pin "7") (pinfunction "PB6(XTAL1/TOSC1)_7") (pintype "bidirectional"))
    )
    (net (code "60") (name "Net-(U$1-OUT)") (class "Default")
      (node (ref "R4") (pin "1") (pinfunction "1_1") (pintype "passive"))
      (node (ref "U$1") (pin "3") (pinfunction "OUT_3") (pintype "bidirectional"))
      (node (ref "U1") (pin "8") (pinfunction "PB7(XTAL2/TOSC2)_8") (pintype "bidirectional"))
    )
    (net (code "61") (name "Net-(U1-AREF)") (class "Default")
      (node (ref "C24") (pin "2") (pinfunction "2_2") (pintype "passive"))
      (node (ref "U1") (pin "20") (pinfunction "AREF_20") (pintype "bidirectional"))
    )
    (net (code "62") (name "Net-(U4-Y)") (class "Default")
      (node (ref "R12") (pin "2") (pinfunction "2_2") (pintype "passive"))
      (node (ref "U4") (pin "4") (pinfunction "Y_4") (pintype "output"))
    )
    (net (code "63") (name "Net-(U5-Y)") (class "Default")
      (node (ref "R11") (pin "2") (pinfunction "2_2") (pintype "passive"))
      (node (ref "U5") (pin "4") (pinfunction "Y_4") (pintype "output"))
    )
    (net (code "64") (name "Net-(U6-A)") (class "Default")
      (node (ref "J4") (pin "1") (pinfunction "1_1") (pintype "passive"))
      (node (ref "U6") (pin "2") (pinfunction "A_2") (pintype "bidirectional"))
    )
    (net (code "65") (name "RESET") (class "Default")
      (node (ref "C23") (pin "2") (pinfunction "2_2") (pintype "passive"))
      (node (ref "R1") (pin "2") (pinfunction "2_2") (pintype "passive"))
      (node (ref "U1") (pin "29") (pinfunction "PC6(/RESET)_29") (pintype "bidirectional"))
    )
    (net (code "66") (name "SCK") (class "Default")
      (node (ref "J3") (pin "3") (pinfunction "3_3") (pintype "bidirectional"))
      (node (ref "U1") (pin "17") (pinfunction "PB5(SCK)_17") (pintype "bidirectional"))
    )
    (net (code "67") (name "VCC") (class "Default")
      (node (ref "C18") (pin "1") (pinfunction "1_1") (pintype "passive"))
      (node (ref "C19") (pin "1") (pinfunction "1_1") (pintype "passive"))
      (node (ref "C20") (pin "1") (pinfunction "1_1") (pintype "passive"))
      (node (ref "C22") (pin "+") (pinfunction "+_+") (pintype "passive"))
      (node (ref "D1") (pin "7SEG3") (pinfunction "CA1_7SEG3") (pintype "passive"))
      (node (ref "D1") (pin "7SEG8") (pinfunction "CA2_7SEG8") (pintype "passive"))
      (node (ref "F1") (pin "2") (pinfunction "2_2") (pintype "bidirectional"))
      (node (ref "J3") (pin "1") (pinfunction "1_1") (pintype "bidirectional"))
      (node (ref "LED1") (pin "2") (pinfunction "VDD_2") (pintype "power_in"))
      (node (ref "LED10") (pin "2") (pinfunction "VDD_2") (pintype "power_in"))
      (node (ref "LED11") (pin "2") (pinfunction "VDD_2") (pintype "power_in"))
      (node (ref "LED12") (pin "2") (pinfunction "VDD_2") (pintype "power_in"))
      (node (ref "LED13") (pin "2") (pinfunction "VDD_2") (pintype "power_in"))
      (node (ref "LED14") (pin "2") (pinfunction "VDD_2") (pintype "power_in"))
      (node (ref "LED15") (pin "2") (pinfunction "VDD_2") (pintype "power_in"))
      (node (ref "LED16") (pin "2") (pinfunction "VDD_2") (pintype "power_in"))
      (node (ref "LED2") (pin "2") (pinfunction "VDD_2") (pintype "power_in"))
      (node (ref "LED3") (pin "2") (pinfunction "VDD_2") (pintype "power_in"))
      (node (ref "LED4") (pin "2") (pinfunction "VDD_2") (pintype "power_in"))
      (node (ref "LED5") (pin "2") (pinfunction "VDD_2") (pintype "power_in"))
      (node (ref "LED6") (pin "2") (pinfunction "VDD_2") (pintype "power_in"))
      (node (ref "LED7") (pin "2") (pinfunction "VDD_2") (pintype "power_in"))
      (node (ref "LED8") (pin "2") (pinfunction "VDD_2") (pintype "power_in"))
      (node (ref "LED9") (pin "2") (pinfunction "VDD_2") (pintype "power_in"))
      (node (ref "R1") (pin "1") (pinfunction "1_1") (pintype "passive"))
      (node (ref "R10") (pin "2") (pinfunction "2_2") (pintype "passive"))
      (node (ref "R6") (pin "2") (pinfunction "2_2") (pintype "passive"))
      (node (ref "R9") (pin "2") (pinfunction "2_2") (pintype "passive"))
      (node (ref "U1") (pin "18") (pinfunction "AVCC_18") (pintype "bidirectional"))
      (node (ref "U1") (pin "4") (pinfunction "VCC_4") (pintype "bidirectional"))
      (node (ref "U1") (pin "6") (pinfunction "VCC_6") (pintype "bidirectional"))
      (node (ref "U2") (pin "10") (pinfunction "SCL_10") (pintype "input"))
      (node (ref "U2") (pin "16") (pinfunction "VCC_16") (pintype "power_in"))
      (node (ref "U4") (pin "5") (pinfunction "VCC_5") (pintype "power_in"))
      (node (ref "U5") (pin "5") (pinfunction "VCC_5") (pintype "power_in"))
      (node (ref "U6") (pin "7") (pinfunction "EN_7") (pintype "bidirectional"))
      (node (ref "U6") (pin "8") (pinfunction "VCC_8") (pintype "bidirectional"))
      (node (ref "V1") (pin "2") (pinfunction "2_2") (pintype "passive"))
    )
    (net (code "68") (name "unconnected-(CN1-PadD+)") (class "Default")
      (node (ref "CN1") (pin "D+") (pinfunction "D+_D+") (pintype "bidirectional"))
    )
    (net (code "69") (name "unconnected-(CN1-PadD-)") (class "Default")
      (node (ref "CN1") (pin "D-") (pinfunction "D-_D-") (pintype "bidirectional"))
    )
    (net (code "70") (name "unconnected-(CN1-PadID)") (class "Default")
      (node (ref "CN1") (pin "ID") (pinfunction "ID_ID") (pintype "bidirectional"))
    )
    (net (code "71") (name "unconnected-(U1-ADC6-Pad19)") (class "Default")
      (node (ref "U1") (pin "19") (pinfunction "ADC6_19") (pintype "bidirectional"))
    )
    (net (code "72") (name "unconnected-(U1-ADC7-Pad22)") (class "Default")
      (node (ref "U1") (pin "22") (pinfunction "ADC7_22") (pintype "bidirectional"))
    )
    (net (code "73") (name "unconnected-(U1-PD2(INT0)-Pad32)") (class "Default")
      (node (ref "U1") (pin "32") (pinfunction "PD2(INT0)_32") (pintype "bidirectional"))
    )
    (net (code "74") (name "unconnected-(U2-QH*-Pad9)") (class "Default")
      (node (ref "U2") (pin "9") (pinfunction "QH*_9") (pintype "tri_state"))
    )
  )
)
